# Power.net
KiCad netlist of a schematic drawn in Altium Designer
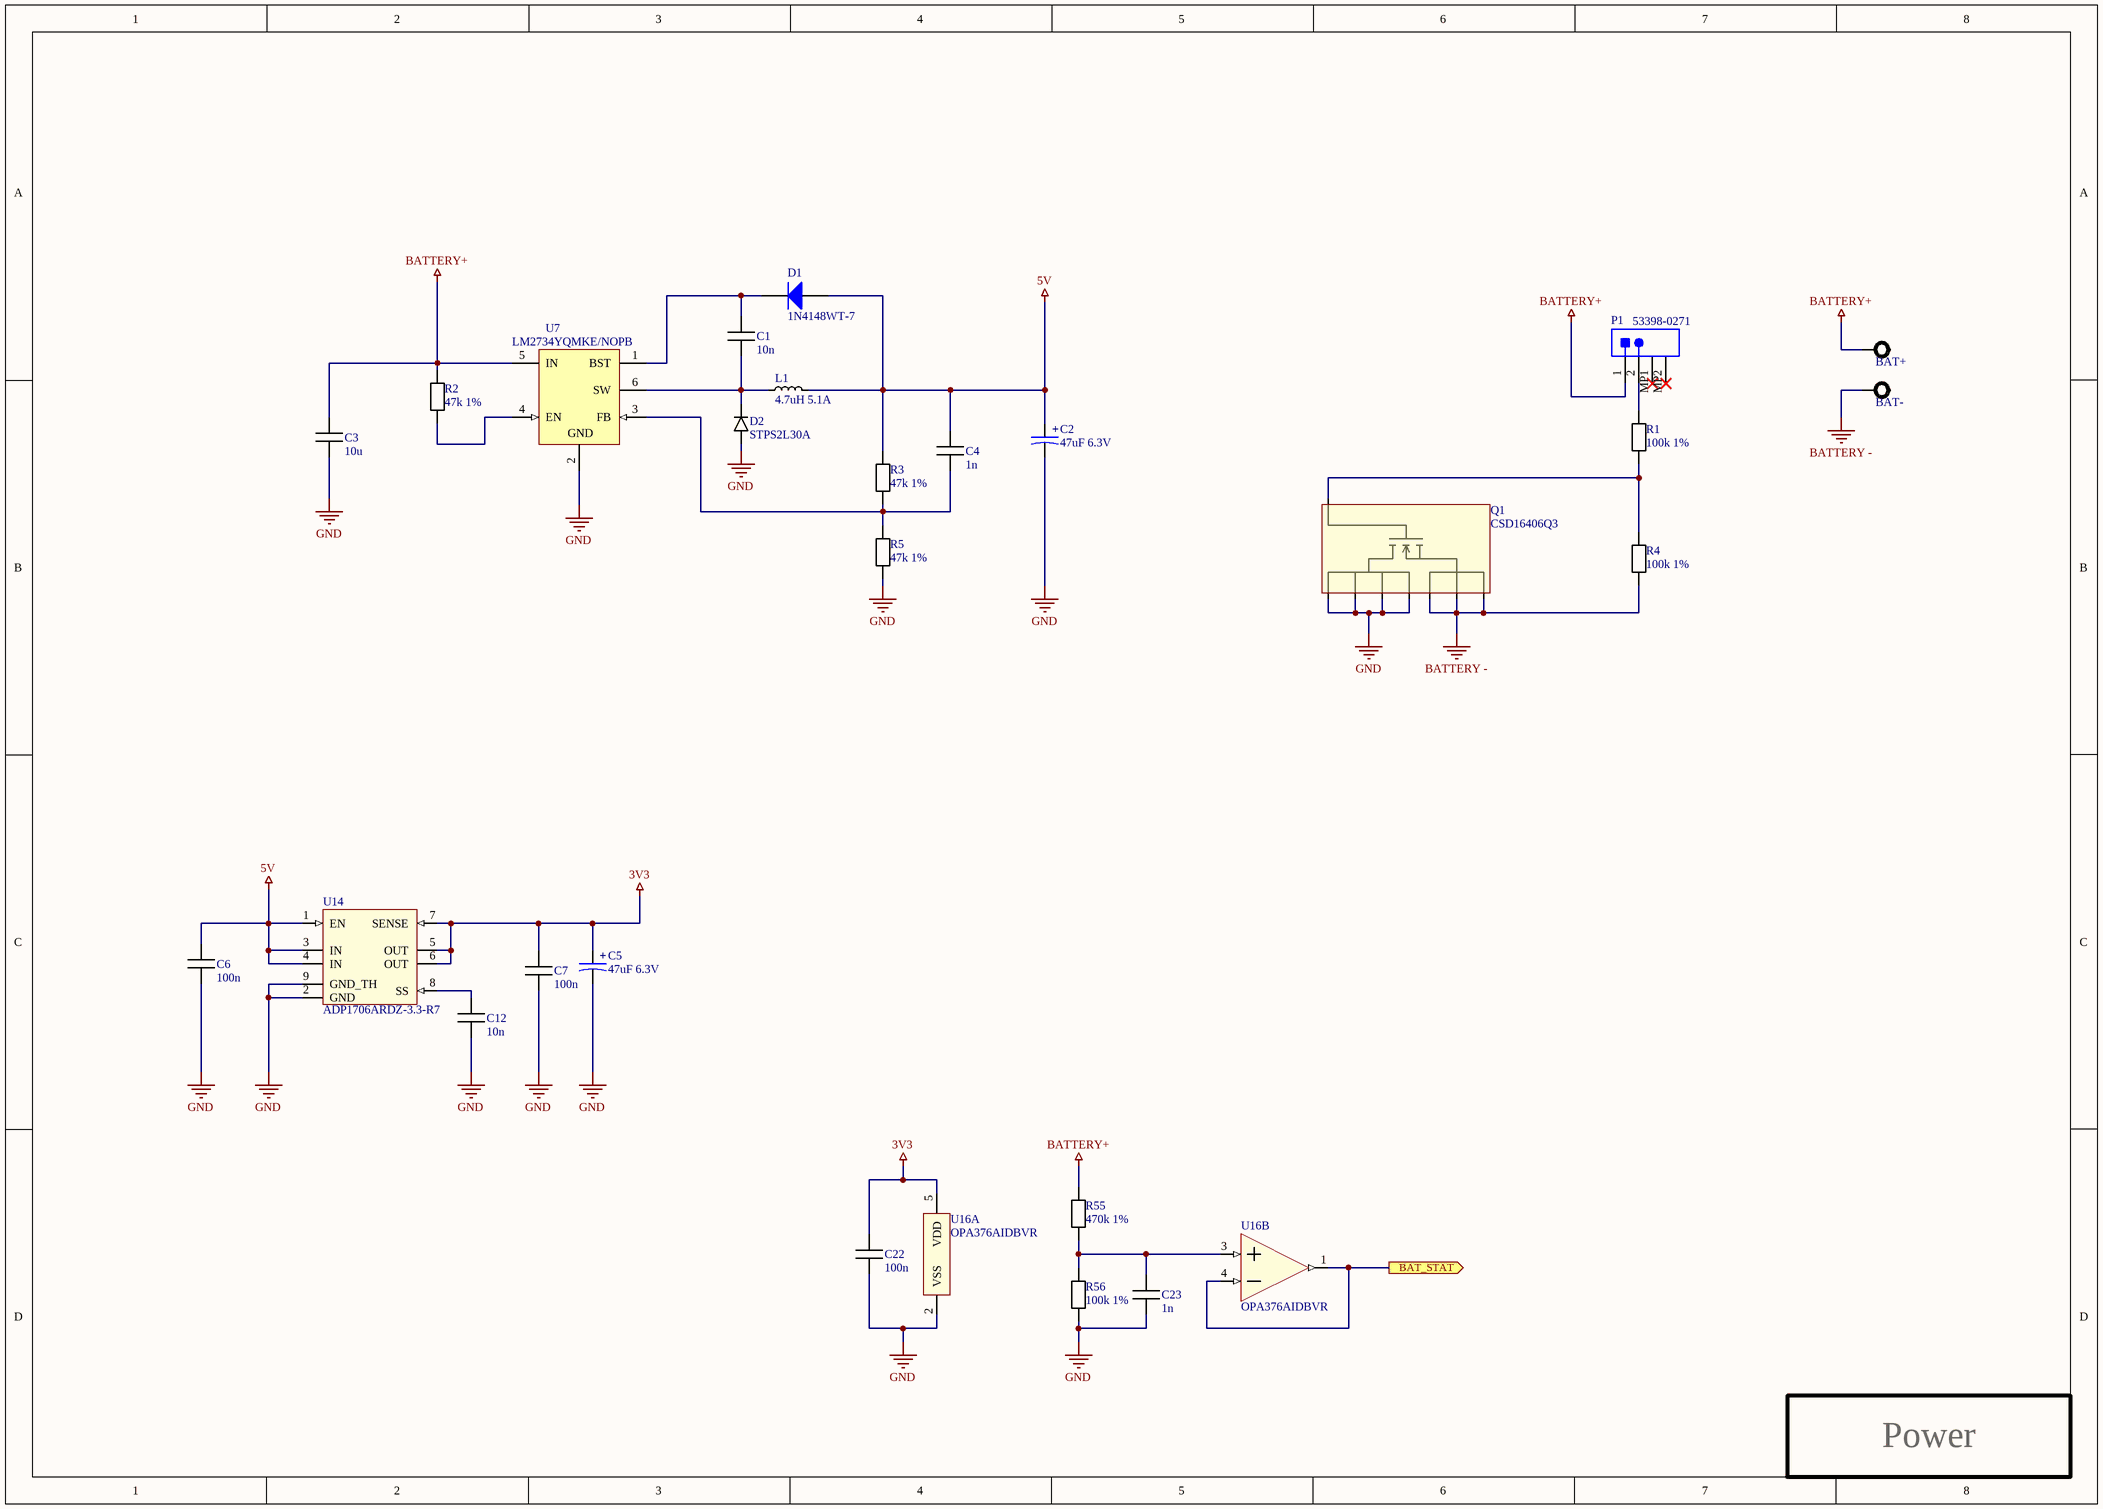
[diagram p0: Power.SchDoc]

(export (version "E")
  (design (tool "Eeschema 10.0.6"))
  (components
    (comp (ref "BAT+")
      (value "1x2mm")
      (footprint "PAD 1x2mm")
      (description "copper pad")
      (fields (field (name "MANUFACTURER") "NA"))
      (libsource (lib "GuowLib") (part "PAD_small"))
    )
    (comp (ref "BAT-")
      (value "1x2mm")
      (footprint "PAD 1x2mm")
      (description "copper pad")
      (fields (field (name "MANUFACTURER") "NA"))
      (libsource (lib "GuowLib") (part "PAD_small"))
    )
    (comp (ref "C1")
      (value "10n")
      (footprint "C_0603_AUTO")
      (fields (field (name "MANUFACTURER") "[Generic]"))
      (libsource (lib "GuowLib") (part "Capacitor"))
    )
    (comp (ref "C2")
      (value "47uF 6.3V")
      (footprint "Kemet_1206")
      (fields (field (name "MPN") "T491A476M006AT") (field (name "MANUFACTURER") "Kemet"))
      (libsource (lib "GuowLib") (part "T491A476M006AT"))
    )
    (comp (ref "C3")
      (value "10u")
      (footprint "C_0805_HAND")
      (fields (field (name "MANUFACTURER") "[Generic]"))
      (libsource (lib "GuowLib") (part "Capacitor"))
    )
    (comp (ref "C4")
      (value "1n")
      (footprint "C_0603_AUTO")
      (fields (field (name "MANUFACTURER") "[Generic]"))
      (libsource (lib "GuowLib") (part "Capacitor"))
    )
    (comp (ref "C5")
      (value "47uF 6.3V")
      (footprint "Kemet_1206")
      (fields (field (name "MPN") "T491A476M006AT") (field (name "MANUFACTURER") "Kemet"))
      (libsource (lib "GuowLib") (part "T491A476M006AT"))
    )
    (comp (ref "C6")
      (value "100n")
      (footprint "C_0603_AUTO")
      (fields (field (name "MANUFACTURER") "[Generic]"))
      (libsource (lib "GuowLib") (part "Capacitor"))
    )
    (comp (ref "C7")
      (value "100n")
      (footprint "C_0603_AUTO")
      (fields (field (name "MANUFACTURER") "[Generic]"))
      (libsource (lib "GuowLib") (part "Capacitor"))
    )
    (comp (ref "C12")
      (value "10n")
      (footprint "C_0603_AUTO")
      (fields (field (name "MANUFACTURER") "[Generic]"))
      (libsource (lib "GuowLib") (part "Capacitor"))
    )
    (comp (ref "C22")
      (value "100n")
      (footprint "C_0603_AUTO")
      (fields (field (name "MANUFACTURER") "[Generic]"))
      (libsource (lib "GuowLib") (part "Capacitor"))
    )
    (comp (ref "C23")
      (value "1n")
      (footprint "C_0603_AUTO")
      (fields (field (name "MANUFACTURER") "[Generic]"))
      (libsource (lib "GuowLib") (part "Capacitor"))
    )
    (comp (ref "D1")
      (value "1N4148WT-7")
      (footprint "DIOD-SOD523-2_V")
      (description "Surface Mount Fast Switching Diode, -65 to 150 degC, 2-Pin SOD523, RoHS, Tape and Reel")
      (fields (field (name "MANUFACTURER") "Diodes Inc") (field (name "PARTNUMBER") "1N4148WT"))
      (libsource (lib "Altium Content Vault") (part "D-KA-2"))
    )
    (comp (ref "D2")
      (value "STPS2L30A")
      (footprint "SMA")
      (description "Schottky Diodes & Rectifiers 2.0 Amp 30 Volt")
      (fields (field (name "MANUFACTURER") "STMicroelectronics"))
      (libsource (lib "GuowLib") (part "STPS2L30A"))
    )
    (comp (ref "L1")
      (value "4.7uH 5.1A")
      (footprint "XAL4030")
      (description "Fixed Inductor 4.7uH 20% 5.1A 44.1mOhms")
      (fields (field (name "MPN") "XAL4030-472") (field (name "MANUFACTURER") "Coilcraft"))
      (libsource (lib "GuowLib") (part "XAL4030-472"))
    )
    (comp (ref "P1")
      (value "53398-0271")
      (footprint "MOLX-53398-0271_V")
      (description "Male Header, Pitch 1.25 mm, 1 x 2 Position, Height 4.7 mm, -40 to 85 degC, RoHS, Tape and Reel")
      (fields (field (name "MANUFACTURER") "Molex"))
      (libsource (lib "Altium Content Vault") (part "CN-1P-2M-R2"))
    )
    (comp (ref "Q1")
      (value "CSD16406Q3")
      (footprint "SON8")
      (description "N-Channel NexFET™ Power MOSFET")
      (fields (field (name "MANUFACTURER") "Texas Instruments"))
      (libsource (lib "GuowLib") (part "CSD16406Q3"))
    )
    (comp (ref "R1")
      (value "100k 1%")
      (footprint "R_0603_AUTO")
      (fields (field (name "MPN") "[Generic]"))
      (libsource (lib "GuowLib") (part "Resistor"))
    )
    (comp (ref "R2")
      (value "47k 1%")
      (footprint "R_0603_AUTO")
      (fields (field (name "MPN") "[Generic]"))
      (libsource (lib "GuowLib") (part "Resistor"))
    )
    (comp (ref "R3")
      (value "47k 1%")
      (footprint "R_0603_AUTO")
      (fields (field (name "MPN") "[Generic]"))
      (libsource (lib "GuowLib") (part "Resistor"))
    )
    (comp (ref "R4")
      (value "100k 1%")
      (footprint "R_0603_AUTO")
      (fields (field (name "MPN") "[Generic]"))
      (libsource (lib "GuowLib") (part "Resistor"))
    )
    (comp (ref "R5")
      (value "47k 1%")
      (footprint "R_0603_AUTO")
      (fields (field (name "MPN") "[Generic]"))
      (libsource (lib "GuowLib") (part "Resistor"))
    )
    (comp (ref "R55")
      (value "470k 1%")
      (footprint "R_0603_AUTO")
      (fields (field (name "MPN") "[Generic]"))
      (libsource (lib "GuowLib") (part "Resistor"))
    )
    (comp (ref "R56")
      (value "100k 1%")
      (footprint "R_0603_AUTO")
      (fields (field (name "MPN") "[Generic]"))
      (libsource (lib "GuowLib") (part "Resistor"))
    )
    (comp (ref "U7")
      (value "LM2734YQMKE/NOPB")
      (footprint "DDC0006A_L")
      (description "1A Load Step-Down DC-DC Regulator, 6-pin Tiny SOT23, Pb-Free")
      (fields (field (name "MANUFACTURER") "Texas Instruments"))
      (libsource (lib "Altium Content Vault") (part "PM-DCDC-LM2734QMK-6"))
    )
    (comp (ref "U14")
      (value "ADP1706ARDZ-3.3-R7")
      (footprint "SOIC-8_HAND_THERM")
      (description "LDO 3V3 1A Slow-Start, 450uV RMS noise")
      (fields (field (name "MANUFACTURER") "Analog Devices"))
      (libsource (lib "GuowLib") (part "ADP1706ARDZ-3.3-R7"))
    )
    (comp (ref "U16")
      (value "OPA376AIDBVR")
      (footprint "SOT23-5_AUTO")
      (description "OP Amp Single R-R 5-Pin SOT-23 T/R Ultra Low Offset")
      (fields (field (name "MANUFACTURER") "Texas Instruments"))
      (libsource (lib "GuowLib") (part "OPA376AIDBVR"))
    )
  )
  (nets
    (net (code "1") (name "/BAT_STAT") (class "Default")
      (node (ref "U16") (pin "1") (pinfunction "OUT_1") (pintype "output"))
      (node (ref "U16") (pin "4") (pinfunction "IN-_4") (pintype "input"))
    )
    (net (code "2") (name "3V3") (class "Default")
      (node (ref "C22") (pin "2") (pinfunction "2_2") (pintype "passive"))
      (node (ref "C5") (pin "1") (pinfunction "1_1") (pintype "passive"))
      (node (ref "C7") (pin "2") (pinfunction "2_2") (pintype "passive"))
      (node (ref "U14") (pin "5") (pinfunction "OUT_5") (pintype "power_in"))
      (node (ref "U14") (pin "6") (pinfunction "OUT_6") (pintype "power_in"))
      (node (ref "U14") (pin "7") (pinfunction "SENSE_7") (pintype "input"))
      (node (ref "U16") (pin "5") (pinfunction "VDD_5") (pintype "power_in"))
    )
    (net (code "3") (name "5V") (class "Default")
      (node (ref "C2") (pin "1") (pinfunction "1_1") (pintype "passive"))
      (node (ref "C4") (pin "2") (pinfunction "2_2") (pintype "passive"))
      (node (ref "C6") (pin "2") (pinfunction "2_2") (pintype "passive"))
      (node (ref "D1") (pin "2") (pinfunction "A_2") (pintype "passive"))
      (node (ref "L1") (pin "2") (pinfunction "2_2") (pintype "passive"))
      (node (ref "R3") (pin "2") (pinfunction "2_2") (pintype "passive"))
      (node (ref "U14") (pin "1") (pinfunction "EN_1") (pintype "input"))
      (node (ref "U14") (pin "3") (pinfunction "IN_3") (pintype "power_in"))
      (node (ref "U14") (pin "4") (pinfunction "IN_4") (pintype "power_in"))
    )
    (net (code "4") (name "BATTERY -") (class "Default")
      (node (ref "BAT-") (pin "1") (pinfunction "1_1") (pintype "passive"))
      (node (ref "Q1") (pin "1") (pinfunction "S_1") (pintype "passive"))
      (node (ref "Q1") (pin "2") (pinfunction "S_2") (pintype "passive"))
      (node (ref "Q1") (pin "3") (pinfunction "S_3") (pintype "passive"))
      (node (ref "R4") (pin "1") (pinfunction "1_1") (pintype "passive"))
    )
    (net (code "5") (name "BATTERY+") (class "Default")
      (node (ref "BAT+") (pin "1") (pinfunction "1_1") (pintype "passive"))
      (node (ref "C3") (pin "2") (pinfunction "2_2") (pintype "passive"))
      (node (ref "P1") (pin "1") (pinfunction "1_1") (pintype "passive"))
      (node (ref "R2") (pin "2") (pinfunction "2_2") (pintype "passive"))
      (node (ref "R55") (pin "2") (pinfunction "2_2") (pintype "passive"))
      (node (ref "U7") (pin "5") (pinfunction "IN_5") (pintype "power_in"))
    )
    (net (code "6") (name "GND") (class "Default")
      (node (ref "C12") (pin "1") (pinfunction "1_1") (pintype "passive"))
      (node (ref "C2") (pin "2") (pinfunction "2_2") (pintype "passive"))
      (node (ref "C22") (pin "1") (pinfunction "1_1") (pintype "passive"))
      (node (ref "C23") (pin "1") (pinfunction "1_1") (pintype "passive"))
      (node (ref "C3") (pin "1") (pinfunction "1_1") (pintype "passive"))
      (node (ref "C5") (pin "2") (pinfunction "2_2") (pintype "passive"))
      (node (ref "C6") (pin "1") (pinfunction "1_1") (pintype "passive"))
      (node (ref "C7") (pin "1") (pinfunction "1_1") (pintype "passive"))
      (node (ref "D2") (pin "1") (pinfunction "A_1") (pintype "passive"))
      (node (ref "Q1") (pin "5") (pinfunction "S_5") (pintype "passive"))
      (node (ref "Q1") (pin "6") (pinfunction "S_6") (pintype "passive"))
      (node (ref "Q1") (pin "7") (pinfunction "S_7") (pintype "passive"))
      (node (ref "Q1") (pin "8") (pinfunction "S_8") (pintype "passive"))
      (node (ref "R5") (pin "1") (pinfunction "1_1") (pintype "passive"))
      (node (ref "R56") (pin "1") (pinfunction "1_1") (pintype "passive"))
      (node (ref "U14") (pin "2") (pinfunction "GND_2") (pintype "power_in"))
      (node (ref "U14") (pin "9") (pinfunction "GND_TH_9") (pintype "power_in"))
      (node (ref "U16") (pin "2") (pinfunction "VSS_2") (pintype "power_in"))
      (node (ref "U7") (pin "2") (pinfunction "GND_2") (pintype "power_in"))
    )
    (net (code "7") (name "Net-(D1-K)") (class "Default")
      (node (ref "C1") (pin "2") (pinfunction "2_2") (pintype "passive"))
      (node (ref "D1") (pin "1") (pinfunction "K_1") (pintype "passive"))
      (node (ref "U7") (pin "1") (pinfunction "BST_1") (pintype "passive"))
    )
    (net (code "8") (name "Net-(D2-C)") (class "Default")
      (node (ref "C1") (pin "1") (pinfunction "1_1") (pintype "passive"))
      (node (ref "D2") (pin "2") (pinfunction "C_2") (pintype "passive"))
      (node (ref "L1") (pin "1") (pinfunction "1_1") (pintype "passive"))
      (node (ref "U7") (pin "6") (pinfunction "SW_6") (pintype "power_in"))
    )
    (net (code "9") (name "Net-(P1-Pad2)") (class "Default")
      (node (ref "P1") (pin "2") (pinfunction "2_2") (pintype "passive"))
      (node (ref "R1") (pin "2") (pinfunction "2_2") (pintype "passive"))
    )
    (net (code "10") (name "Net-(Q1-S-Pad4)") (class "Default")
      (node (ref "Q1") (pin "4") (pinfunction "S_4") (pintype "passive"))
      (node (ref "R1") (pin "1") (pinfunction "1_1") (pintype "passive"))
      (node (ref "R4") (pin "2") (pinfunction "2_2") (pintype "passive"))
    )
    (net (code "11") (name "Net-(U7-EN)") (class "Default")
      (node (ref "R2") (pin "1") (pinfunction "1_1") (pintype "passive"))
      (node (ref "U7") (pin "4") (pinfunction "EN_4") (pintype "input"))
    )
    (net (code "12") (name "Net-(U7-FB)") (class "Default")
      (node (ref "C4") (pin "1") (pinfunction "1_1") (pintype "passive"))
      (node (ref "R3") (pin "1") (pinfunction "1_1") (pintype "passive"))
      (node (ref "R5") (pin "2") (pinfunction "2_2") (pintype "passive"))
      (node (ref "U7") (pin "3") (pinfunction "FB_3") (pintype "input"))
    )
    (net (code "13") (name "Net-(U14-SS)") (class "Default")
      (node (ref "C12") (pin "2") (pinfunction "2_2") (pintype "passive"))
      (node (ref "U14") (pin "8") (pinfunction "SS_8") (pintype "input"))
    )
    (net (code "14") (name "Net-(U16B-IN+)") (class "Default")
      (node (ref "C23") (pin "2") (pinfunction "2_2") (pintype "passive"))
      (node (ref "R55") (pin "1") (pinfunction "1_1") (pintype "passive"))
      (node (ref "R56") (pin "2") (pinfunction "2_2") (pintype "passive"))
      (node (ref "U16") (pin "3") (pinfunction "IN+_3") (pintype "input"))
    )
    (net (code "15") (name "unconnected-(P1-PadMP1)") (class "Default")
      (node (ref "P1") (pin "MP1") (pinfunction "MP1_MP1") (pintype "passive+no_connect"))
    )
    (net (code "16") (name "unconnected-(P1-PadMP2)") (class "Default")
      (node (ref "P1") (pin "MP2") (pinfunction "MP2_MP2") (pintype "passive+no_connect"))
    )
  )
)
